# TSOC_NEOLED_R1_0.net
KiCad netlist of a schematic drawn in EAGLE
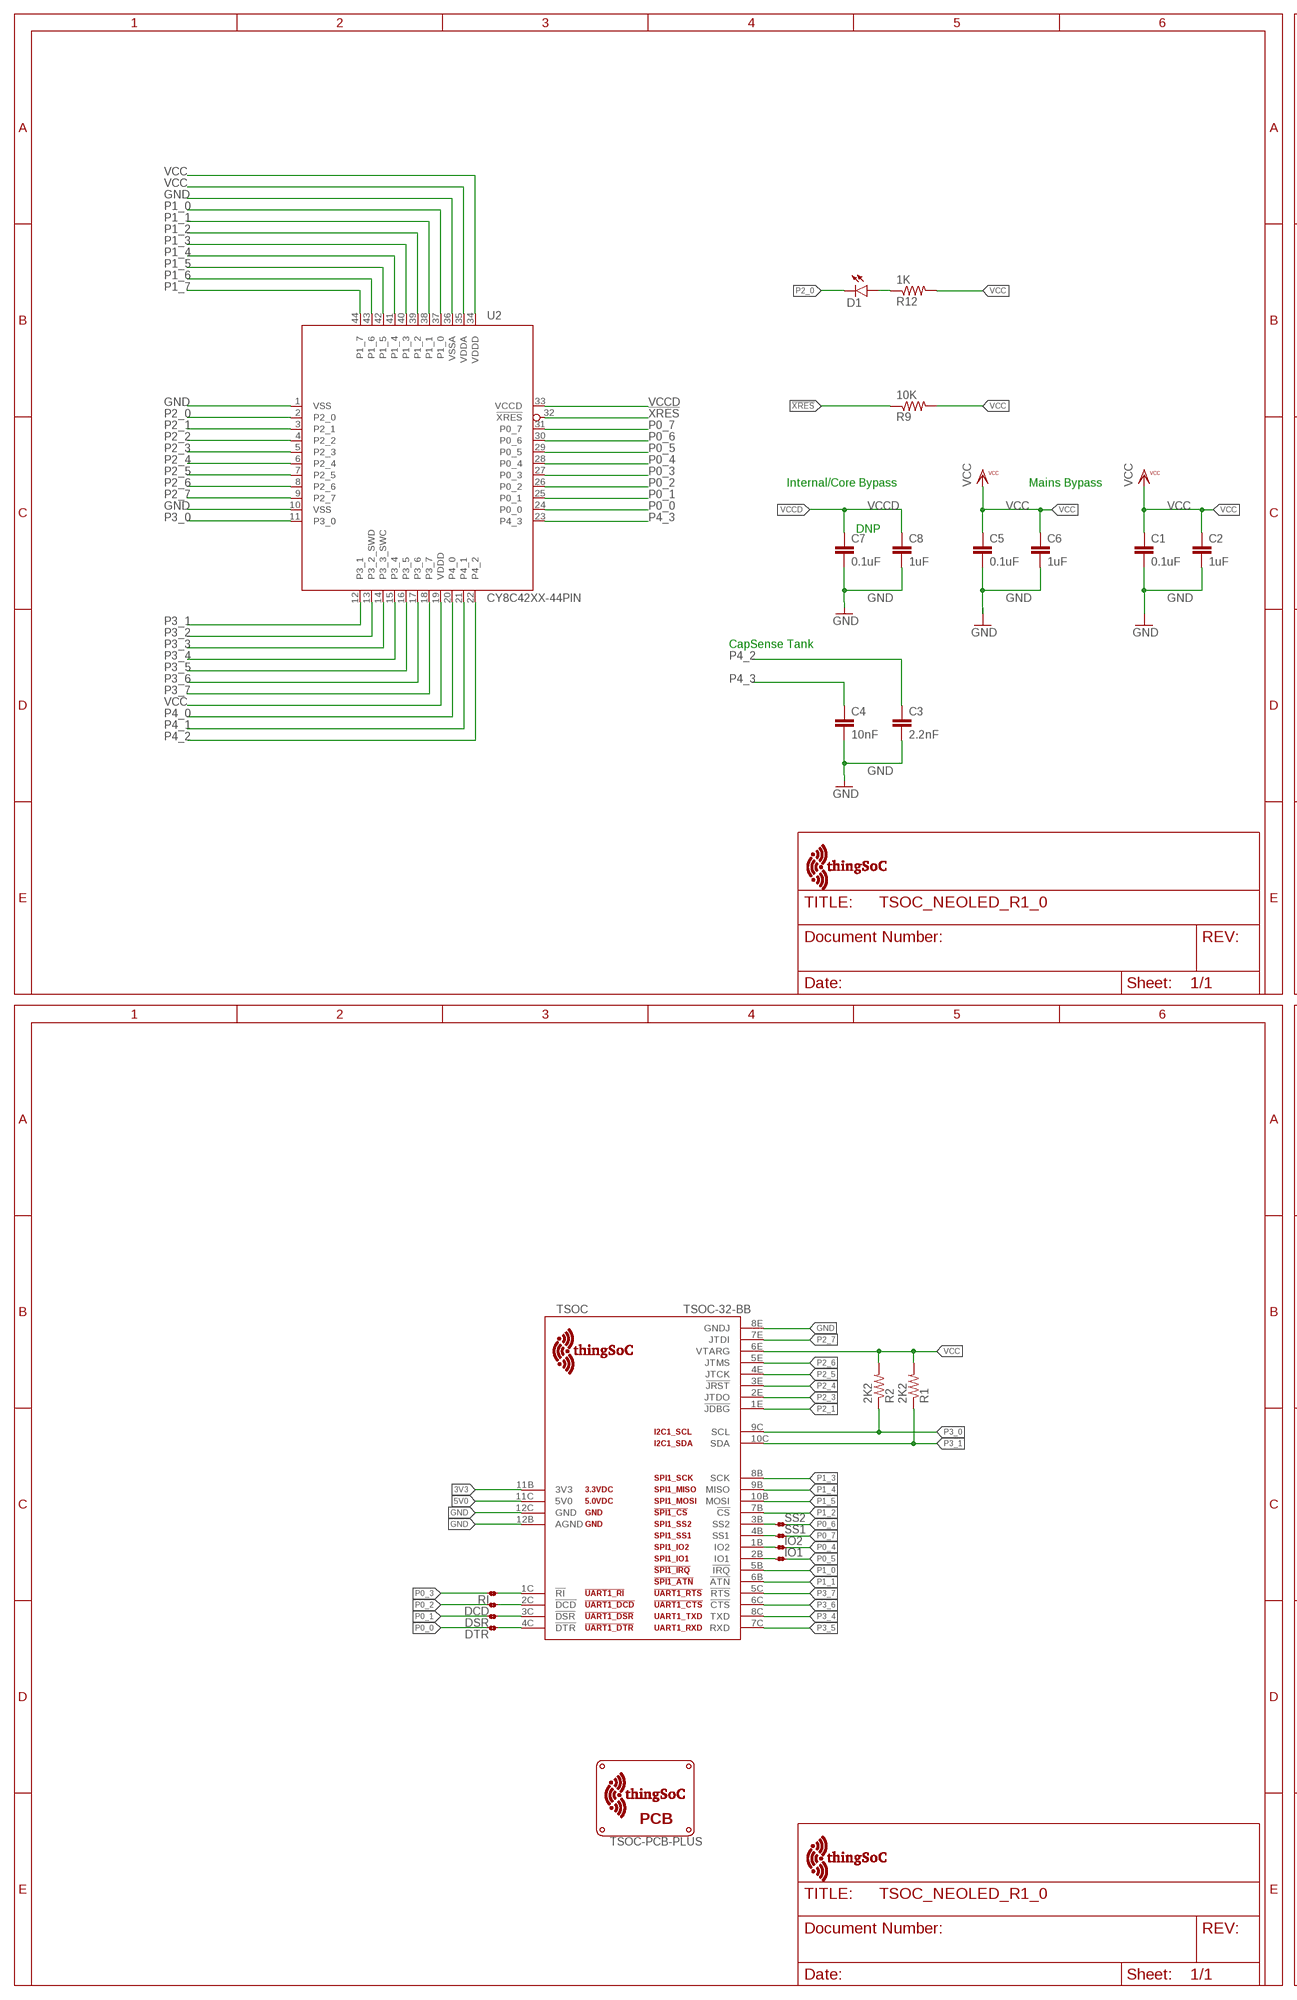
[diagram p0: schematic, sheet 1, part 1 of 2]
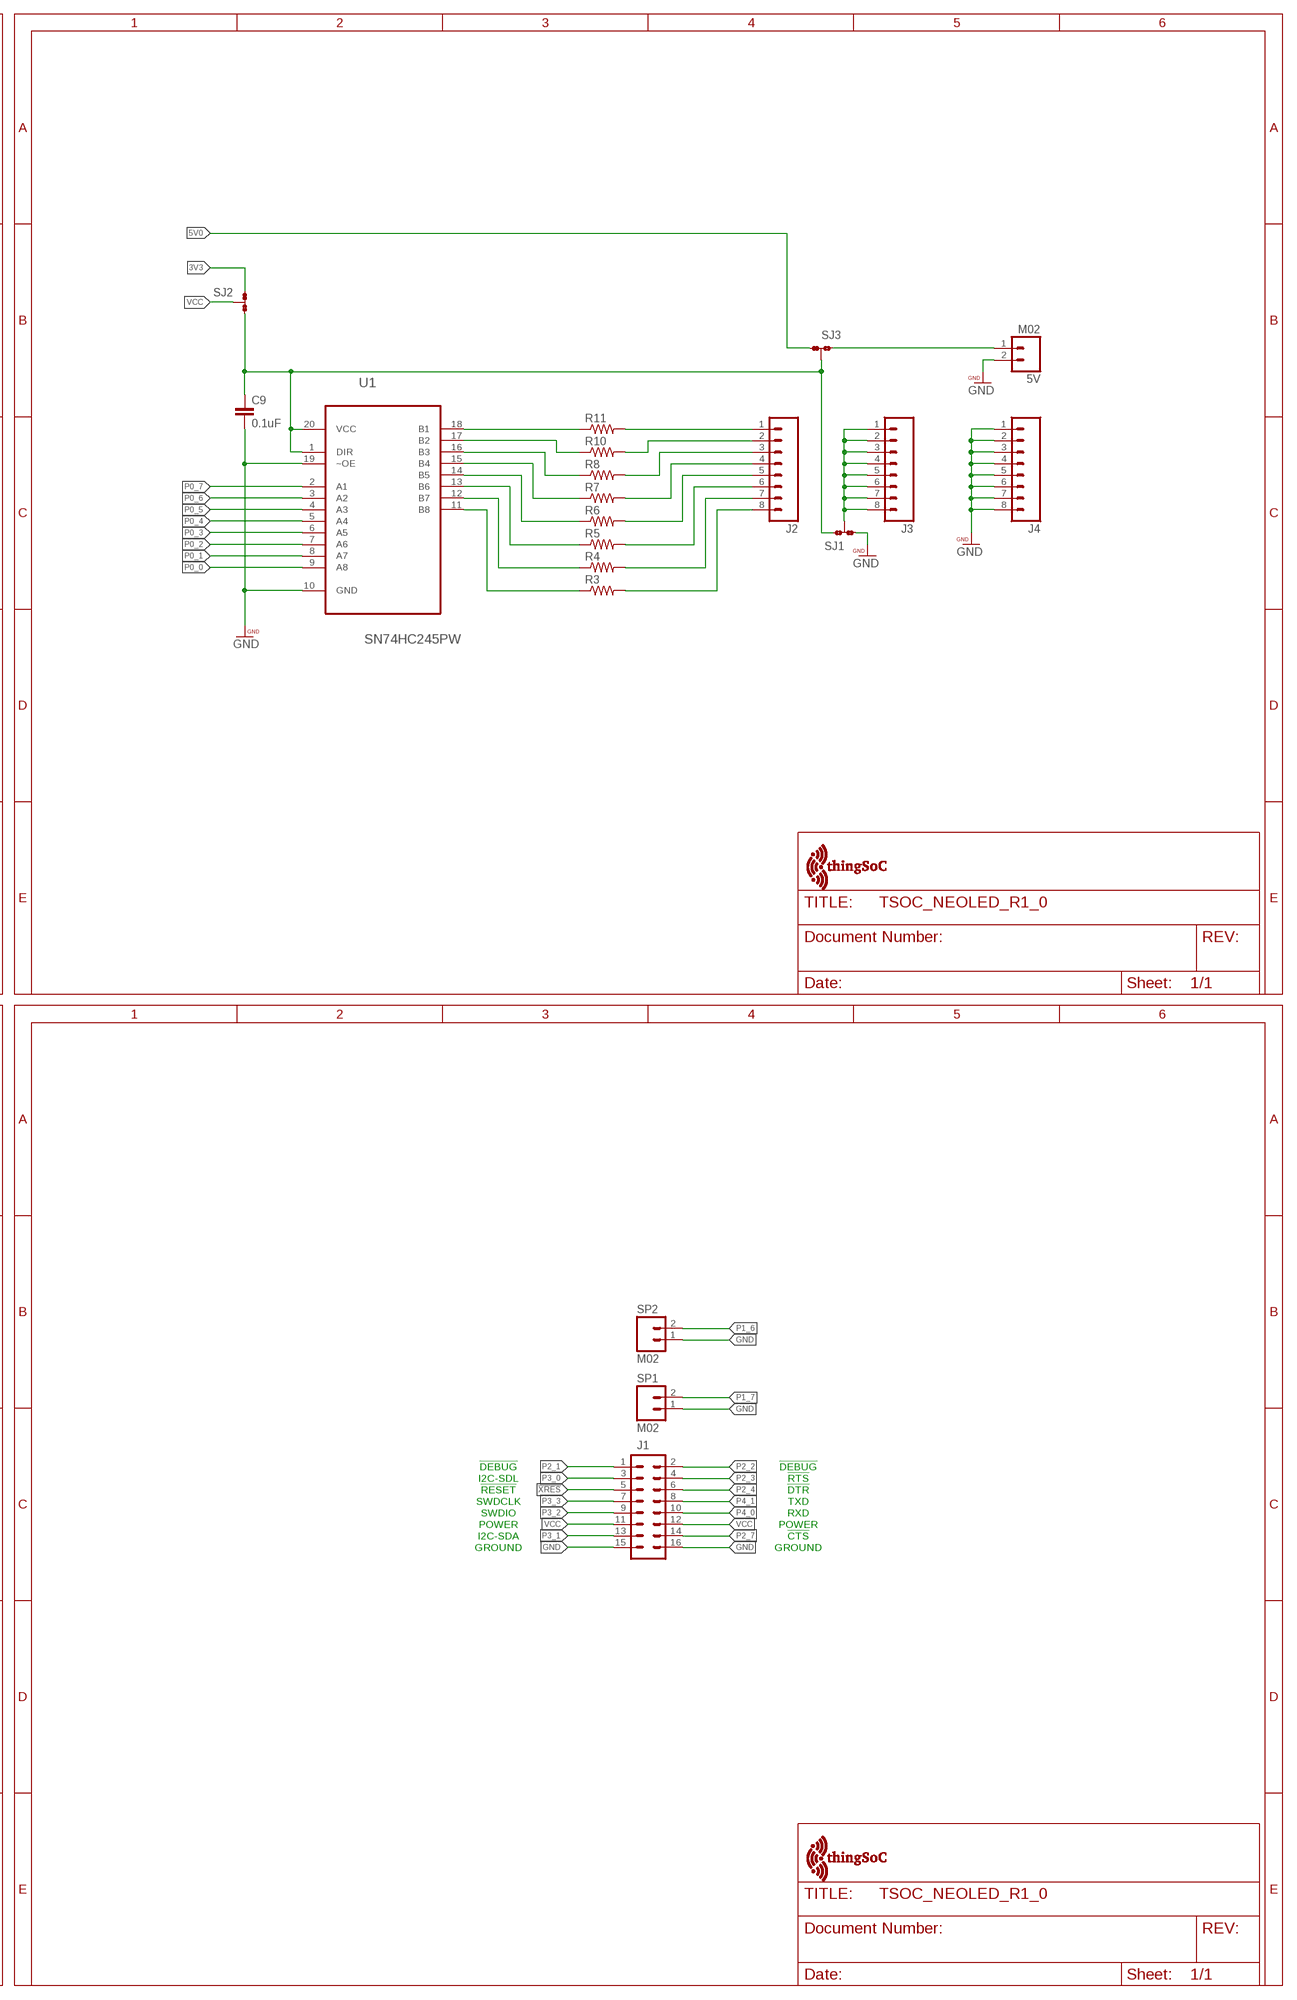
[diagram p1: schematic, sheet 1, part 2 of 2]

(export (version "E")
  (design (tool "Eeschema 10.0.6"))
  (components
    (comp (ref "$$U$1")
      (value "TSOC-LOGO-SMALL")
      (footprint "eagle-import:TSOC-LOGO-SML")
      (libsource (lib "eagle-import") (part "TSOC-LOGO-SMALL"))
    )
    (comp (ref "$$U$2")
      (value "TSOC-LOGO-MED")
      (footprint "eagle-import:TSOC-LOGO-MED")
      (libsource (lib "eagle-import") (part "TSOC-LOGO-MED"))
    )
    (comp (ref "5V")
      (value "M02")
      (footprint "eagle-import:1X02")
      (libsource (lib "eagle-import") (part "M02"))
    )
    (comp (ref "C1")
      (value "0.1uF")
      (footprint "eagle-import:0603-CAP")
      (libsource (lib "eagle-import") (part "CAP0603-CAP"))
    )
    (comp (ref "C2")
      (value "1uF")
      (footprint "eagle-import:0603-CAP")
      (libsource (lib "eagle-import") (part "CAP0603-CAP"))
    )
    (comp (ref "C3")
      (value "2.2nF")
      (footprint "eagle-import:0603-CAP")
      (libsource (lib "eagle-import") (part "CAP0603-CAP"))
    )
    (comp (ref "C4")
      (value "10nF")
      (footprint "eagle-import:0603-CAP")
      (libsource (lib "eagle-import") (part "CAP0603-CAP"))
    )
    (comp (ref "C5")
      (value "0.1uF")
      (footprint "eagle-import:0603-CAP")
      (libsource (lib "eagle-import") (part "CAP0603-CAP"))
    )
    (comp (ref "C6")
      (value "1uF")
      (footprint "eagle-import:0603-CAP")
      (libsource (lib "eagle-import") (part "CAP0603-CAP"))
    )
    (comp (ref "C7")
      (value "0.1uF")
      (footprint "eagle-import:0603-CAP")
      (libsource (lib "eagle-import") (part "CAP0603-CAP"))
    )
    (comp (ref "C8")
      (value "1uF")
      (footprint "eagle-import:0603-CAP")
      (libsource (lib "eagle-import") (part "CAP0603-CAP"))
    )
    (comp (ref "C9")
      (value "0.1uF")
      (footprint "eagle-import:0603-CAP")
      (libsource (lib "eagle-import") (part "CAP0603-CAP"))
    )
    (comp (ref "D1")
      (value "LED0603")
      (footprint "eagle-import:LED-0603")
      (libsource (lib "eagle-import") (part "LED0603"))
    )
    (comp (ref "DCD")
      (value "JMP-2-NO")
      (footprint "eagle-import:JMP-2-NO")
      (libsource (lib "eagle-import") (part "JMP-2-NO"))
    )
    (comp (ref "DSR")
      (value "JMP-2-NO")
      (footprint "eagle-import:JMP-2-NO")
      (libsource (lib "eagle-import") (part "JMP-2-NO"))
    )
    (comp (ref "DTR")
      (value "JMP-2-NO")
      (footprint "eagle-import:JMP-2-NO")
      (libsource (lib "eagle-import") (part "JMP-2-NO"))
    )
    (comp (ref "IO1")
      (value "JMP-2-NO")
      (footprint "eagle-import:JMP-2-NO")
      (libsource (lib "eagle-import") (part "JMP-2-NO"))
    )
    (comp (ref "IO2")
      (value "JMP-2-NO")
      (footprint "eagle-import:JMP-2-NO")
      (libsource (lib "eagle-import") (part "JMP-2-NO"))
    )
    (comp (ref "J1")
      (value "M08X2")
      (footprint "eagle-import:2X8")
      (libsource (lib "eagle-import") (part "M08X2"))
    )
    (comp (ref "J2")
      (value "M08")
      (footprint "eagle-import:1X08_ROUND")
      (libsource (lib "eagle-import") (part "M08"))
    )
    (comp (ref "J3")
      (value "M08")
      (footprint "eagle-import:1X08_ROUND")
      (libsource (lib "eagle-import") (part "M08"))
    )
    (comp (ref "J4")
      (value "M08")
      (footprint "eagle-import:1X08_ROUND")
      (libsource (lib "eagle-import") (part "M08"))
    )
    (comp (ref "R1")
      (value "2K2")
      (footprint "eagle-import:0603-RES")
      (libsource (lib "eagle-import") (part "RESISTOR_SFE0603-RES"))
    )
    (comp (ref "R2")
      (value "2K2")
      (footprint "eagle-import:0603-RES")
      (libsource (lib "eagle-import") (part "RESISTOR_SFE0603-RES"))
    )
    (comp (ref "R3")
      (value "RESISTOR0603-RES")
      (footprint "eagle-import:0603-RES")
      (libsource (lib "eagle-import") (part "RESISTOR0603-RES"))
    )
    (comp (ref "R4")
      (value "RESISTOR0603-RES")
      (footprint "eagle-import:0603-RES")
      (libsource (lib "eagle-import") (part "RESISTOR0603-RES"))
    )
    (comp (ref "R5")
      (value "RESISTOR0603-RES")
      (footprint "eagle-import:0603-RES")
      (libsource (lib "eagle-import") (part "RESISTOR0603-RES"))
    )
    (comp (ref "R6")
      (value "RESISTOR0603-RES")
      (footprint "eagle-import:0603-RES")
      (libsource (lib "eagle-import") (part "RESISTOR0603-RES"))
    )
    (comp (ref "R7")
      (value "RESISTOR0603-RES")
      (footprint "eagle-import:0603-RES")
      (libsource (lib "eagle-import") (part "RESISTOR0603-RES"))
    )
    (comp (ref "R8")
      (value "RESISTOR0603-RES")
      (footprint "eagle-import:0603-RES")
      (libsource (lib "eagle-import") (part "RESISTOR0603-RES"))
    )
    (comp (ref "R9")
      (value "10K")
      (footprint "eagle-import:0603-RES")
      (libsource (lib "eagle-import") (part "RESISTOR_SFE0603-RES"))
    )
    (comp (ref "R10")
      (value "RESISTOR0603-RES")
      (footprint "eagle-import:0603-RES")
      (libsource (lib "eagle-import") (part "RESISTOR0603-RES"))
    )
    (comp (ref "R11")
      (value "RESISTOR0603-RES")
      (footprint "eagle-import:0603-RES")
      (libsource (lib "eagle-import") (part "RESISTOR0603-RES"))
    )
    (comp (ref "R12")
      (value "1K")
      (footprint "eagle-import:0603-RES")
      (libsource (lib "eagle-import") (part "RESISTOR_SFE0603-RES"))
    )
    (comp (ref "RI")
      (value "JMP-2-NO")
      (footprint "eagle-import:JMP-2-NO")
      (libsource (lib "eagle-import") (part "JMP-2-NO"))
    )
    (comp (ref "SJ1")
      (value "JMP-3-1_2")
      (footprint "eagle-import:JMP-3-1_2")
      (libsource (lib "eagle-import") (part "JMP-3-1_2"))
    )
    (comp (ref "SJ2")
      (value "JMP-3-1_2")
      (footprint "eagle-import:JMP-3-1_2")
      (libsource (lib "eagle-import") (part "JMP-3-1_2"))
    )
    (comp (ref "SJ3")
      (value "JMP-3-1_2")
      (footprint "eagle-import:JMP-3-1_2")
      (libsource (lib "eagle-import") (part "JMP-3-1_2"))
    )
    (comp (ref "SP1")
      (value "M02")
      (footprint "eagle-import:1X02")
      (libsource (lib "eagle-import") (part "M02"))
    )
    (comp (ref "SP2")
      (value "M02")
      (footprint "eagle-import:1X02")
      (libsource (lib "eagle-import") (part "M02"))
    )
    (comp (ref "SS1")
      (value "JMP-2-NO")
      (footprint "eagle-import:JMP-2-NO")
      (libsource (lib "eagle-import") (part "JMP-2-NO"))
    )
    (comp (ref "SS2")
      (value "JMP-2-NO")
      (footprint "eagle-import:JMP-2-NO")
      (libsource (lib "eagle-import") (part "JMP-2-NO"))
    )
    (comp (ref "TSOC")
      (value "TSOC-32-BB")
      (footprint "eagle-import:TSOC-BB-S32")
      (libsource (lib "eagle-import") (part "TSOC-32-BB"))
    )
    (comp (ref "U$3")
      (value "TSOC-PCB-PLUS")
      (footprint "eagle-import:TSOC-BB-BRD-PLUS")
      (libsource (lib "eagle-import") (part "TSOC-PCB-PLUS"))
    )
    (comp (ref "U$100")
      (value "TSOC-LOGO-SMALL")
      (footprint "eagle-import:TSOC-LOGO-SML")
      (libsource (lib "eagle-import") (part "TSOC-LOGO-SMALL"))
    )
    (comp (ref "U$101")
      (value "TSOC-LOGO-LRG")
      (footprint "eagle-import:TSOC-LOGO-LRG")
      (libsource (lib "eagle-import") (part "TSOC-LOGO-LRG"))
    )
    (comp (ref "U1")
      (value "SN74HC245PW")
      (footprint "eagle-import:SOP65P640X120-20N")
      (libsource (lib "eagle-import") (part "SN74HC245PW"))
    )
    (comp (ref "U2")
      (value "CY8C42XX-44PIN")
      (footprint "eagle-import:TQFP-10X10-44")
      (libsource (lib "eagle-import") (part "CY8C42XX-44PIN"))
    )
  )
  (nets
    (net (code "1") (name "/P4_2") (class "Default")
      (node (ref "C3") (pin "1") (pinfunction "1_1") (pintype "passive"))
      (node (ref "U2") (pin "22") (pinfunction "P4_2_22") (pintype "bidirectional"))
    )
    (net (code "2") (name "/P4_3") (class "Default")
      (node (ref "C4") (pin "1") (pinfunction "1_1") (pintype "passive"))
      (node (ref "U2") (pin "23") (pinfunction "P4_3_23") (pintype "bidirectional"))
    )
    (net (code "3") (name "/~{XRES}") (class "Default")
      (node (ref "J1") (pin "5") (pinfunction "5_5") (pintype "passive"))
      (node (ref "R9") (pin "1") (pinfunction "1_1") (pintype "passive"))
      (node (ref "U2") (pin "32") (pinfunction "~{XRES}_32") (pintype "bidirectional"))
    )
    (net (code "4") (name "3V3") (class "Default")
      (node (ref "SJ2") (pin "1") (pinfunction "1_1") (pintype "passive"))
      (node (ref "TSOC") (pin "11B") (pinfunction "3V3_11B") (pintype "bidirectional"))
    )
    (net (code "5") (name "5V0") (class "Default")
      (node (ref "SJ3") (pin "1") (pinfunction "1_1") (pintype "passive"))
      (node (ref "TSOC") (pin "11C") (pinfunction "5V0_11C") (pintype "bidirectional"))
    )
    (net (code "6") (name "GND") (class "Default")
      (node (ref "5V") (pin "2") (pinfunction "2_2") (pintype "passive"))
      (node (ref "C1") (pin "2") (pinfunction "2_2") (pintype "passive"))
      (node (ref "C2") (pin "2") (pinfunction "2_2") (pintype "passive"))
      (node (ref "C3") (pin "2") (pinfunction "2_2") (pintype "passive"))
      (node (ref "C4") (pin "2") (pinfunction "2_2") (pintype "passive"))
      (node (ref "C5") (pin "2") (pinfunction "2_2") (pintype "passive"))
      (node (ref "C6") (pin "2") (pinfunction "2_2") (pintype "passive"))
      (node (ref "C7") (pin "2") (pinfunction "2_2") (pintype "passive"))
      (node (ref "C8") (pin "2") (pinfunction "2_2") (pintype "passive"))
      (node (ref "C9") (pin "2") (pinfunction "2_2") (pintype "passive"))
      (node (ref "J1") (pin "15") (pinfunction "15_15") (pintype "passive"))
      (node (ref "J1") (pin "16") (pinfunction "16_16") (pintype "passive"))
      (node (ref "J4") (pin "1") (pinfunction "1_1") (pintype "passive"))
      (node (ref "J4") (pin "2") (pinfunction "2_2") (pintype "passive"))
      (node (ref "J4") (pin "3") (pinfunction "3_3") (pintype "passive"))
      (node (ref "J4") (pin "4") (pinfunction "4_4") (pintype "passive"))
      (node (ref "J4") (pin "5") (pinfunction "5_5") (pintype "passive"))
      (node (ref "J4") (pin "6") (pinfunction "6_6") (pintype "passive"))
      (node (ref "J4") (pin "7") (pinfunction "7_7") (pintype "passive"))
      (node (ref "J4") (pin "8") (pinfunction "8_8") (pintype "passive"))
      (node (ref "SJ1") (pin "1") (pinfunction "1_1") (pintype "passive"))
      (node (ref "SP1") (pin "1") (pinfunction "1_1") (pintype "passive"))
      (node (ref "SP2") (pin "1") (pinfunction "1_1") (pintype "passive"))
      (node (ref "TSOC") (pin "12B") (pinfunction "AGND_12B") (pintype "bidirectional"))
      (node (ref "TSOC") (pin "12C") (pinfunction "GND_12C") (pintype "bidirectional"))
      (node (ref "TSOC") (pin "8E") (pinfunction "GNDJ_8E") (pintype "bidirectional"))
      (node (ref "U1") (pin "10") (pinfunction "GND_10") (pintype "input"))
      (node (ref "U1") (pin "19") (pinfunction "~{OE}_19") (pintype "input"))
      (node (ref "U2") (pin "1") (pinfunction "VSS_1") (pintype "bidirectional"))
      (node (ref "U2") (pin "10") (pinfunction "VSS_10") (pintype "bidirectional"))
      (node (ref "U2") (pin "36") (pinfunction "VSSA_36") (pintype "bidirectional"))
    )
    (net (code "7") (name "Net-(5V-Pad1)") (class "Default")
      (node (ref "5V") (pin "1") (pinfunction "1_1") (pintype "passive"))
      (node (ref "SJ3") (pin "3") (pinfunction "3_3") (pintype "passive"))
    )
    (net (code "8") (name "Net-(D1-PadA)") (class "Default")
      (node (ref "D1") (pin "A") (pinfunction "A_A") (pintype "passive"))
      (node (ref "R12") (pin "1") (pinfunction "1_1") (pintype "passive"))
    )
    (net (code "9") (name "Net-(J2-Pad1)") (class "Default")
      (node (ref "J2") (pin "1") (pinfunction "1_1") (pintype "passive"))
      (node (ref "R11") (pin "2") (pinfunction "2_2") (pintype "passive"))
    )
    (net (code "10") (name "Net-(J2-Pad2)") (class "Default")
      (node (ref "J2") (pin "2") (pinfunction "2_2") (pintype "passive"))
      (node (ref "R10") (pin "2") (pinfunction "2_2") (pintype "passive"))
    )
    (net (code "11") (name "Net-(J2-Pad3)") (class "Default")
      (node (ref "J2") (pin "3") (pinfunction "3_3") (pintype "passive"))
      (node (ref "R8") (pin "2") (pinfunction "2_2") (pintype "passive"))
    )
    (net (code "12") (name "Net-(J2-Pad4)") (class "Default")
      (node (ref "J2") (pin "4") (pinfunction "4_4") (pintype "passive"))
      (node (ref "R7") (pin "2") (pinfunction "2_2") (pintype "passive"))
    )
    (net (code "13") (name "Net-(J2-Pad5)") (class "Default")
      (node (ref "J2") (pin "5") (pinfunction "5_5") (pintype "passive"))
      (node (ref "R6") (pin "2") (pinfunction "2_2") (pintype "passive"))
    )
    (net (code "14") (name "Net-(J2-Pad6)") (class "Default")
      (node (ref "J2") (pin "6") (pinfunction "6_6") (pintype "passive"))
      (node (ref "R5") (pin "2") (pinfunction "2_2") (pintype "passive"))
    )
    (net (code "15") (name "Net-(J2-Pad7)") (class "Default")
      (node (ref "J2") (pin "7") (pinfunction "7_7") (pintype "passive"))
      (node (ref "R4") (pin "2") (pinfunction "2_2") (pintype "passive"))
    )
    (net (code "16") (name "Net-(J2-Pad8)") (class "Default")
      (node (ref "J2") (pin "8") (pinfunction "8_8") (pintype "passive"))
      (node (ref "R3") (pin "2") (pinfunction "2_2") (pintype "passive"))
    )
    (net (code "17") (name "Net-(J3-Pad1)") (class "Default")
      (node (ref "J3") (pin "1") (pinfunction "1_1") (pintype "passive"))
      (node (ref "J3") (pin "2") (pinfunction "2_2") (pintype "passive"))
      (node (ref "J3") (pin "3") (pinfunction "3_3") (pintype "passive"))
      (node (ref "J3") (pin "4") (pinfunction "4_4") (pintype "passive"))
      (node (ref "J3") (pin "5") (pinfunction "5_5") (pintype "passive"))
      (node (ref "J3") (pin "6") (pinfunction "6_6") (pintype "passive"))
      (node (ref "J3") (pin "7") (pinfunction "7_7") (pintype "passive"))
      (node (ref "J3") (pin "8") (pinfunction "8_8") (pintype "passive"))
      (node (ref "SJ1") (pin "2") (pinfunction "2_2") (pintype "passive"))
    )
    (net (code "18") (name "Net-(TSOC-IO1)") (class "Default")
      (node (ref "IO1") (pin "1") (pinfunction "1_1") (pintype "passive"))
      (node (ref "TSOC") (pin "2B") (pinfunction "IO1_2B") (pintype "bidirectional"))
    )
    (net (code "19") (name "Net-(TSOC-IO2)") (class "Default")
      (node (ref "IO2") (pin "1") (pinfunction "1_1") (pintype "passive"))
      (node (ref "TSOC") (pin "1B") (pinfunction "IO2_1B") (pintype "bidirectional"))
    )
    (net (code "20") (name "Net-(TSOC-SS1)") (class "Default")
      (node (ref "SS1") (pin "1") (pinfunction "1_1") (pintype "passive"))
      (node (ref "TSOC") (pin "4B") (pinfunction "SS1_4B") (pintype "bidirectional"))
    )
    (net (code "21") (name "Net-(TSOC-SS2)") (class "Default")
      (node (ref "SS2") (pin "1") (pinfunction "1_1") (pintype "passive"))
      (node (ref "TSOC") (pin "3B") (pinfunction "SS2_3B") (pintype "bidirectional"))
    )
    (net (code "22") (name "Net-(TSOC-~{DCD})") (class "Default")
      (node (ref "DCD") (pin "1") (pinfunction "1_1") (pintype "passive"))
      (node (ref "TSOC") (pin "2C") (pinfunction "~{DCD}_2C") (pintype "bidirectional"))
    )
    (net (code "23") (name "Net-(TSOC-~{DSR})") (class "Default")
      (node (ref "DSR") (pin "1") (pinfunction "1_1") (pintype "passive"))
      (node (ref "TSOC") (pin "3C") (pinfunction "~{DSR}_3C") (pintype "bidirectional"))
    )
    (net (code "24") (name "Net-(TSOC-~{DTR})") (class "Default")
      (node (ref "DTR") (pin "1") (pinfunction "1_1") (pintype "passive"))
      (node (ref "TSOC") (pin "4C") (pinfunction "~{DTR}_4C") (pintype "bidirectional"))
    )
    (net (code "25") (name "Net-(TSOC-~{RI})") (class "Default")
      (node (ref "RI") (pin "1") (pinfunction "1_1") (pintype "passive"))
      (node (ref "TSOC") (pin "1C") (pinfunction "~{RI}_1C") (pintype "bidirectional"))
    )
    (net (code "26") (name "Net-(U1-B1)") (class "Default")
      (node (ref "R11") (pin "1") (pinfunction "1_1") (pintype "passive"))
      (node (ref "U1") (pin "18") (pinfunction "B1_18") (pintype "bidirectional"))
    )
    (net (code "27") (name "Net-(U1-B2)") (class "Default")
      (node (ref "R10") (pin "1") (pinfunction "1_1") (pintype "passive"))
      (node (ref "U1") (pin "17") (pinfunction "B2_17") (pintype "bidirectional"))
    )
    (net (code "28") (name "Net-(U1-B3)") (class "Default")
      (node (ref "R8") (pin "1") (pinfunction "1_1") (pintype "passive"))
      (node (ref "U1") (pin "16") (pinfunction "B3_16") (pintype "bidirectional"))
    )
    (net (code "29") (name "Net-(U1-B4)") (class "Default")
      (node (ref "R7") (pin "1") (pinfunction "1_1") (pintype "passive"))
      (node (ref "U1") (pin "15") (pinfunction "B4_15") (pintype "bidirectional"))
    )
    (net (code "30") (name "Net-(U1-B5)") (class "Default")
      (node (ref "R6") (pin "1") (pinfunction "1_1") (pintype "passive"))
      (node (ref "U1") (pin "14") (pinfunction "B5_14") (pintype "bidirectional"))
    )
    (net (code "31") (name "Net-(U1-B6)") (class "Default")
      (node (ref "R5") (pin "1") (pinfunction "1_1") (pintype "passive"))
      (node (ref "U1") (pin "13") (pinfunction "B6_13") (pintype "bidirectional"))
    )
    (net (code "32") (name "Net-(U1-B7)") (class "Default")
      (node (ref "R4") (pin "1") (pinfunction "1_1") (pintype "passive"))
      (node (ref "U1") (pin "12") (pinfunction "B7_12") (pintype "bidirectional"))
    )
    (net (code "33") (name "Net-(U1-B8)") (class "Default")
      (node (ref "R3") (pin "1") (pinfunction "1_1") (pintype "passive"))
      (node (ref "U1") (pin "11") (pinfunction "B8_11") (pintype "bidirectional"))
    )
    (net (code "34") (name "Net-(U1-DIR)") (class "Default")
      (node (ref "C9") (pin "1") (pinfunction "1_1") (pintype "passive"))
      (node (ref "SJ1") (pin "3") (pinfunction "3_3") (pintype "passive"))
      (node (ref "SJ2") (pin "3") (pinfunction "3_3") (pintype "passive"))
      (node (ref "SJ3") (pin "2") (pinfunction "2_2") (pintype "passive"))
      (node (ref "U1") (pin "1") (pinfunction "DIR_1") (pintype "input"))
      (node (ref "U1") (pin "20") (pinfunction "VCC_20") (pintype "power_in"))
    )
    (net (code "35") (name "P0_0") (class "Default")
      (node (ref "DTR") (pin "2") (pinfunction "2_2") (pintype "passive"))
      (node (ref "U1") (pin "9") (pinfunction "A8_9") (pintype "bidirectional"))
      (node (ref "U2") (pin "24") (pinfunction "P0_0_24") (pintype "bidirectional"))
    )
    (net (code "36") (name "P0_1") (class "Default")
      (node (ref "DSR") (pin "2") (pinfunction "2_2") (pintype "passive"))
      (node (ref "U1") (pin "8") (pinfunction "A7_8") (pintype "bidirectional"))
      (node (ref "U2") (pin "25") (pinfunction "P0_1_25") (pintype "bidirectional"))
    )
    (net (code "37") (name "P0_2") (class "Default")
      (node (ref "DCD") (pin "2") (pinfunction "2_2") (pintype "passive"))
      (node (ref "U1") (pin "7") (pinfunction "A6_7") (pintype "bidirectional"))
      (node (ref "U2") (pin "26") (pinfunction "P0_2_26") (pintype "input"))
    )
    (net (code "38") (name "P0_3") (class "Default")
      (node (ref "RI") (pin "2") (pinfunction "2_2") (pintype "passive"))
      (node (ref "U1") (pin "6") (pinfunction "A5_6") (pintype "bidirectional"))
      (node (ref "U2") (pin "27") (pinfunction "P0_3_27") (pintype "bidirectional"))
    )
    (net (code "39") (name "P0_4") (class "Default")
      (node (ref "IO2") (pin "2") (pinfunction "2_2") (pintype "passive"))
      (node (ref "U1") (pin "5") (pinfunction "A4_5") (pintype "bidirectional"))
      (node (ref "U2") (pin "28") (pinfunction "P0_4_28") (pintype "bidirectional"))
    )
    (net (code "40") (name "P0_5") (class "Default")
      (node (ref "IO1") (pin "2") (pinfunction "2_2") (pintype "passive"))
      (node (ref "U1") (pin "4") (pinfunction "A3_4") (pintype "bidirectional"))
      (node (ref "U2") (pin "29") (pinfunction "P0_5_29") (pintype "bidirectional"))
    )
    (net (code "41") (name "P0_6") (class "Default")
      (node (ref "SS2") (pin "2") (pinfunction "2_2") (pintype "passive"))
      (node (ref "U1") (pin "3") (pinfunction "A2_3") (pintype "bidirectional"))
      (node (ref "U2") (pin "30") (pinfunction "P0_6_30") (pintype "power_in"))
    )
    (net (code "42") (name "P0_7") (class "Default")
      (node (ref "SS1") (pin "2") (pinfunction "2_2") (pintype "passive"))
      (node (ref "U1") (pin "2") (pinfunction "A1_2") (pintype "bidirectional"))
      (node (ref "U2") (pin "31") (pinfunction "P0_7_31") (pintype "bidirectional"))
    )
    (net (code "43") (name "P1_0") (class "Default")
      (node (ref "TSOC") (pin "5B") (pinfunction "~{IRQ}_5B") (pintype "bidirectional"))
      (node (ref "U2") (pin "37") (pinfunction "P1_0_37") (pintype "bidirectional"))
    )
    (net (code "44") (name "P1_1") (class "Default")
      (node (ref "TSOC") (pin "6B") (pinfunction "~{ATN}_6B") (pintype "bidirectional"))
      (node (ref "U2") (pin "38") (pinfunction "P1_1_38") (pintype "bidirectional"))
    )
    (net (code "45") (name "P1_2") (class "Default")
      (node (ref "TSOC") (pin "7B") (pinfunction "~{CS}_7B") (pintype "bidirectional"))
      (node (ref "U2") (pin "39") (pinfunction "P1_2_39") (pintype "power_in"))
    )
    (net (code "46") (name "P1_3") (class "Default")
      (node (ref "TSOC") (pin "8B") (pinfunction "SCK_8B") (pintype "bidirectional"))
      (node (ref "U2") (pin "40") (pinfunction "P1_3_40") (pintype "bidirectional"))
    )
    (net (code "47") (name "P1_4") (class "Default")
      (node (ref "TSOC") (pin "9B") (pinfunction "MISO_9B") (pintype "bidirectional"))
      (node (ref "U2") (pin "41") (pinfunction "P1_4_41") (pintype "bidirectional"))
    )
    (net (code "48") (name "P1_5") (class "Default")
      (node (ref "TSOC") (pin "10B") (pinfunction "MOSI_10B") (pintype "bidirectional"))
      (node (ref "U2") (pin "42") (pinfunction "P1_5_42") (pintype "bidirectional"))
    )
    (net (code "49") (name "P1_6") (class "Default")
      (node (ref "SP2") (pin "2") (pinfunction "2_2") (pintype "passive"))
      (node (ref "U2") (pin "43") (pinfunction "P1_6_43") (pintype "bidirectional"))
    )
    (net (code "50") (name "P1_7") (class "Default")
      (node (ref "SP1") (pin "2") (pinfunction "2_2") (pintype "passive"))
      (node (ref "U2") (pin "44") (pinfunction "P1_7_44") (pintype "bidirectional"))
    )
    (net (code "51") (name "P2_0") (class "Default")
      (node (ref "D1") (pin "C") (pinfunction "C_C") (pintype "passive"))
      (node (ref "U2") (pin "2") (pinfunction "P2_0_2") (pintype "bidirectional"))
    )
    (net (code "52") (name "P2_1") (class "Default")
      (node (ref "J1") (pin "1") (pinfunction "1_1") (pintype "passive"))
      (node (ref "TSOC") (pin "1E") (pinfunction "~{JDBG}_1E") (pintype "bidirectional"))
      (node (ref "U2") (pin "3") (pinfunction "P2_1_3") (pintype "bidirectional"))
    )
    (net (code "53") (name "P2_2") (class "Default")
      (node (ref "J1") (pin "2") (pinfunction "2_2") (pintype "passive"))
      (node (ref "U2") (pin "4") (pinfunction "P2_2_4") (pintype "power_in"))
    )
    (net (code "54") (name "P2_3") (class "Default")
      (node (ref "J1") (pin "4") (pinfunction "4_4") (pintype "passive"))
      (node (ref "TSOC") (pin "2E") (pinfunction "JTDO_2E") (pintype "bidirectional"))
      (node (ref "U2") (pin "5") (pinfunction "P2_3_5") (pintype "bidirectional"))
    )
    (net (code "55") (name "P2_4") (class "Default")
      (node (ref "J1") (pin "6") (pinfunction "6_6") (pintype "passive"))
      (node (ref "TSOC") (pin "3E") (pinfunction "~{JRST}_3E") (pintype "bidirectional"))
      (node (ref "U2") (pin "6") (pinfunction "P2_4_6") (pintype "bidirectional"))
    )
    (net (code "56") (name "P2_5") (class "Default")
      (node (ref "TSOC") (pin "4E") (pinfunction "JTCK_4E") (pintype "bidirectional"))
      (node (ref "U2") (pin "7") (pinfunction "P2_5_7") (pintype "bidirectional"))
    )
    (net (code "57") (name "P2_6") (class "Default")
      (node (ref "TSOC") (pin "5E") (pinfunction "JTMS_5E") (pintype "bidirectional"))
      (node (ref "U2") (pin "8") (pinfunction "P2_6_8") (pintype "power_in"))
    )
    (net (code "58") (name "P2_7") (class "Default")
      (node (ref "J1") (pin "14") (pinfunction "14_14") (pintype "passive"))
      (node (ref "TSOC") (pin "7E") (pinfunction "JTDI_7E") (pintype "bidirectional"))
      (node (ref "U2") (pin "9") (pinfunction "P2_7_9") (pintype "bidirectional"))
    )
    (net (code "59") (name "P3_0") (class "Default")
      (node (ref "J1") (pin "3") (pinfunction "3_3") (pintype "passive"))
      (node (ref "R2") (pin "1") (pinfunction "1_1") (pintype "passive"))
      (node (ref "TSOC") (pin "9C") (pinfunction "SCL_9C") (pintype "bidirectional"))
      (node (ref "U2") (pin "11") (pinfunction "P3_0_11") (pintype "bidirectional"))
    )
    (net (code "60") (name "P3_1") (class "Default")
      (node (ref "J1") (pin "13") (pinfunction "13_13") (pintype "passive"))
      (node (ref "R1") (pin "1") (pinfunction "1_1") (pintype "passive"))
      (node (ref "TSOC") (pin "10C") (pinfunction "SDA_10C") (pintype "bidirectional"))
      (node (ref "U2") (pin "12") (pinfunction "P3_1_12") (pintype "bidirectional"))
    )
    (net (code "61") (name "P3_2") (class "Default")
      (node (ref "J1") (pin "9") (pinfunction "9_9") (pintype "passive"))
      (node (ref "U2") (pin "13") (pinfunction "P3_2_SWD_13") (pintype "bidirectional"))
    )
    (net (code "62") (name "P3_3") (class "Default")
      (node (ref "J1") (pin "7") (pinfunction "7_7") (pintype "passive"))
      (node (ref "U2") (pin "14") (pinfunction "P3_3_SWC_14") (pintype "bidirectional"))
    )
    (net (code "63") (name "P3_4") (class "Default")
      (node (ref "TSOC") (pin "8C") (pinfunction "TXD_8C") (pintype "bidirectional"))
      (node (ref "U2") (pin "15") (pinfunction "P3_4_15") (pintype "bidirectional"))
    )
    (net (code "64") (name "P3_5") (class "Default")
      (node (ref "TSOC") (pin "7C") (pinfunction "RXD_7C") (pintype "bidirectional"))
      (node (ref "U2") (pin "16") (pinfunction "P3_5_16") (pintype "bidirectional"))
    )
    (net (code "65") (name "P3_6") (class "Default")
      (node (ref "TSOC") (pin "6C") (pinfunction "~{CTS}_6C") (pintype "bidirectional"))
      (node (ref "U2") (pin "17") (pinfunction "P3_6_17") (pintype "power_in"))
    )
    (net (code "66") (name "P3_7") (class "Default")
      (node (ref "TSOC") (pin "5C") (pinfunction "~{RTS}_5C") (pintype "bidirectional"))
      (node (ref "U2") (pin "18") (pinfunction "P3_7_18") (pintype "bidirectional"))
    )
    (net (code "67") (name "P4_0") (class "Default")
      (node (ref "J1") (pin "10") (pinfunction "10_10") (pintype "passive"))
      (node (ref "U2") (pin "20") (pinfunction "P4_0_20") (pintype "bidirectional"))
    )
    (net (code "68") (name "P4_1") (class "Default")
      (node (ref "J1") (pin "8") (pinfunction "8_8") (pintype "passive"))
      (node (ref "U2") (pin "21") (pinfunction "P4_1_21") (pintype "bidirectional"))
    )
    (net (code "69") (name "VCC") (class "Default")
      (node (ref "C1") (pin "1") (pinfunction "1_1") (pintype "passive"))
      (node (ref "C2") (pin "1") (pinfunction "1_1") (pintype "passive"))
      (node (ref "C5") (pin "1") (pinfunction "1_1") (pintype "passive"))
      (node (ref "C6") (pin "1") (pinfunction "1_1") (pintype "passive"))
      (node (ref "J1") (pin "11") (pinfunction "11_11") (pintype "passive"))
      (node (ref "J1") (pin "12") (pinfunction "12_12") (pintype "passive"))
      (node (ref "R1") (pin "2") (pinfunction "2_2") (pintype "passive"))
      (node (ref "R12") (pin "2") (pinfunction "2_2") (pintype "passive"))
      (node (ref "R2") (pin "2") (pinfunction "2_2") (pintype "passive"))
      (node (ref "R9") (pin "2") (pinfunction "2_2") (pintype "passive"))
      (node (ref "SJ2") (pin "2") (pinfunction "2_2") (pintype "passive"))
      (node (ref "TSOC") (pin "6E") (pinfunction "VTARG_6E") (pintype "bidirectional"))
      (node (ref "U2") (pin "19") (pinfunction "VDDD_19") (pintype "bidirectional"))
      (node (ref "U2") (pin "34") (pinfunction "VDDD_34") (pintype "bidirectional"))
      (node (ref "U2") (pin "35") (pinfunction "VDDA_35") (pintype "bidirectional"))
    )
    (net (code "70") (name "VCCD") (class "Default")
      (node (ref "C7") (pin "1") (pinfunction "1_1") (pintype "passive"))
      (node (ref "C8") (pin "1") (pinfunction "1_1") (pintype "passive"))
      (node (ref "U2") (pin "33") (pinfunction "VCCD_33") (pintype "bidirectional"))
    )
  )
)
